# SparkFun_FT245-Breakout.net
KiCad netlist of a schematic drawn in EAGLE
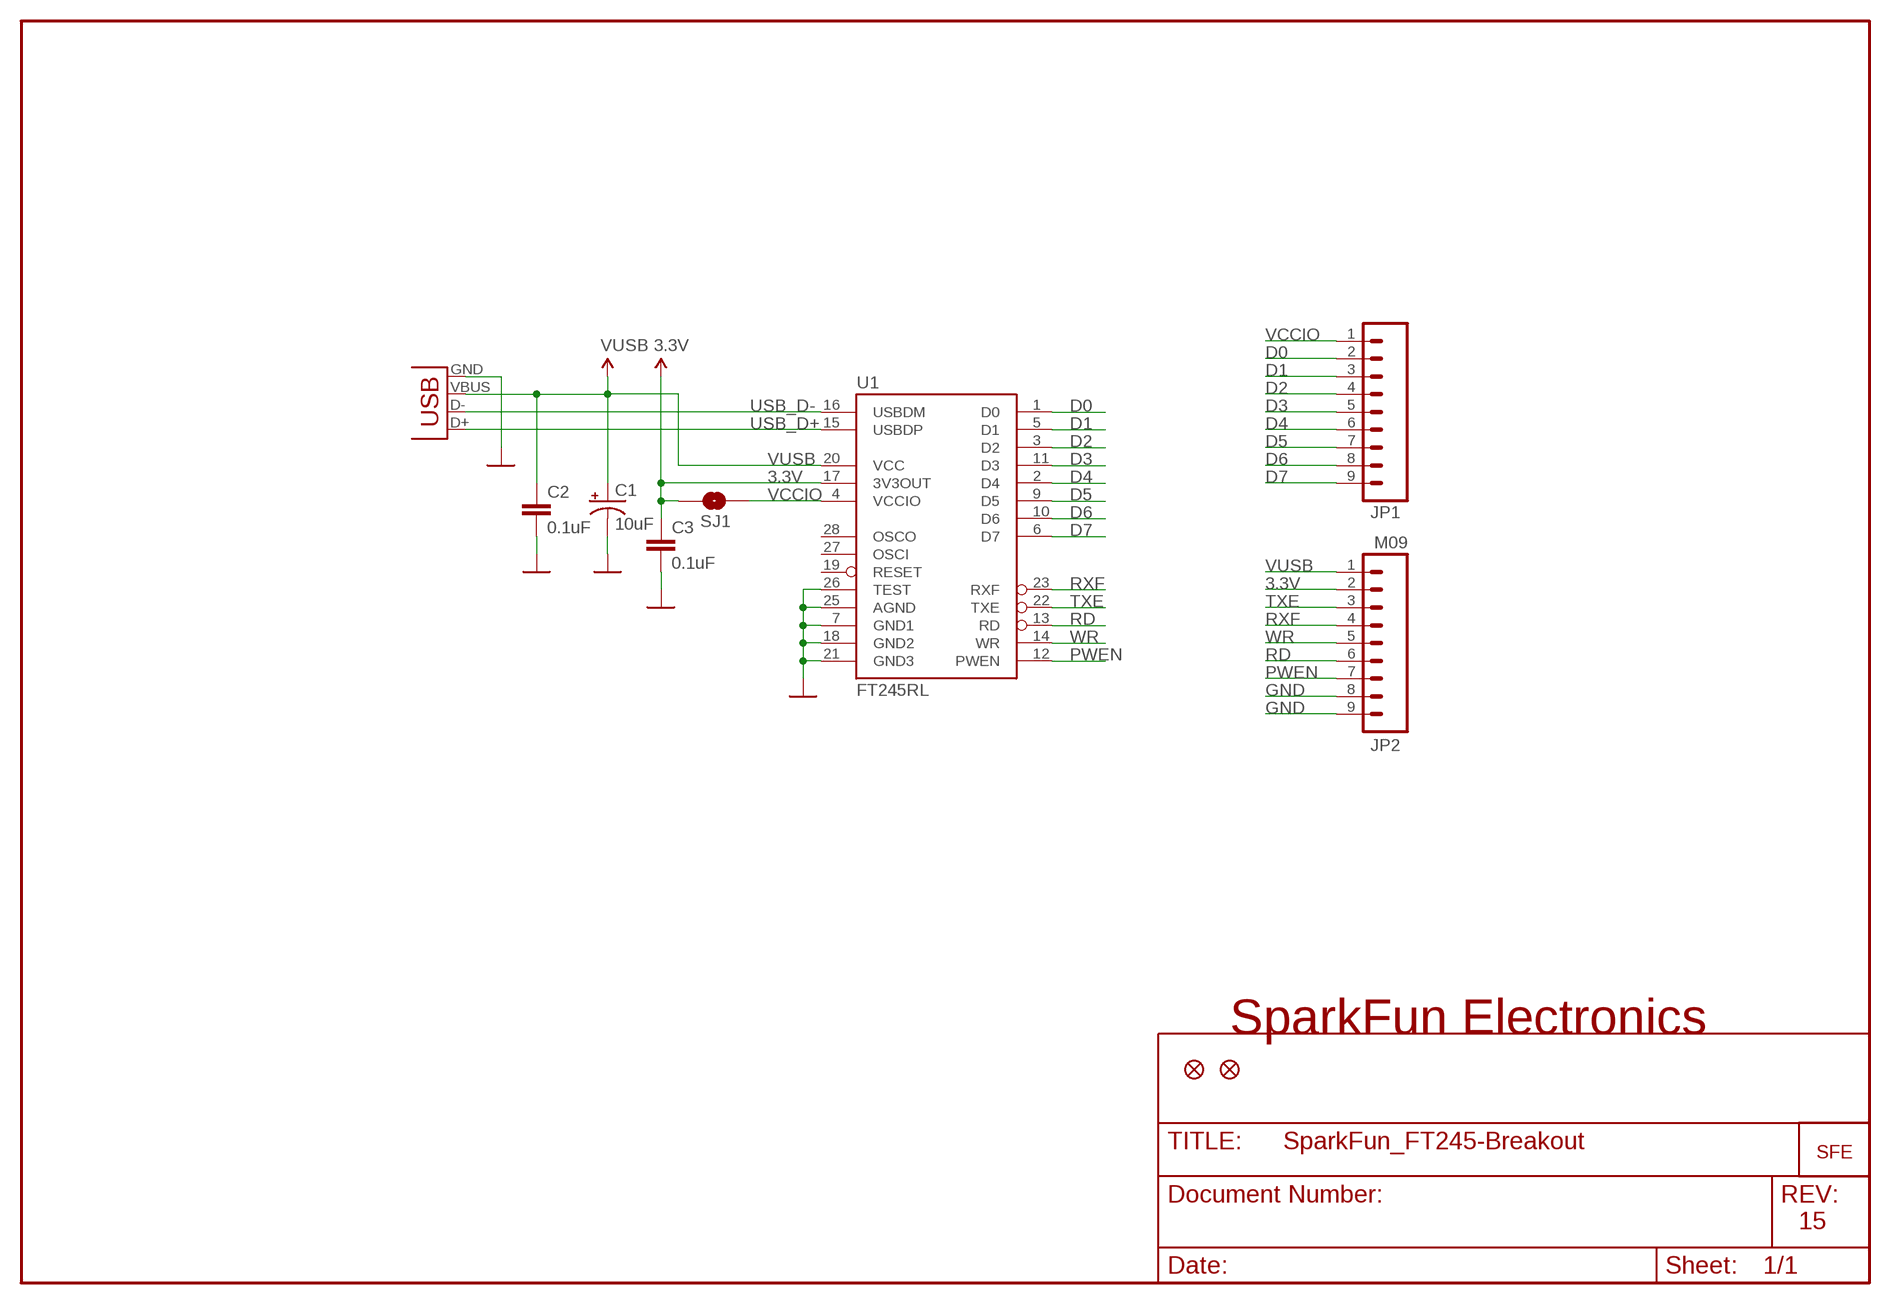
[diagram p0: schematic, sheet 1]

(export (version "E")
  (design (tool "Eeschema 10.0.6"))
  (components
    (comp (ref "C1")
      (value "10uF")
      (footprint "eagle-import:CPOL_1206")
      (libsource (lib "eagle-import") (part "CAP_POL1206"))
    )
    (comp (ref "C2")
      (value "0.1uF")
      (footprint "eagle-import:0402-CAP")
      (libsource (lib "eagle-import") (part "CAP0402-CAP"))
    )
    (comp (ref "C3")
      (value "0.1uF")
      (footprint "eagle-import:0402-CAP")
      (libsource (lib "eagle-import") (part "CAP0402-CAP"))
    )
    (comp (ref "JP1")
      (value "M09")
      (footprint "eagle-import:1X09")
      (libsource (lib "eagle-import") (part "M09"))
    )
    (comp (ref "JP2")
      (value "M09")
      (footprint "eagle-import:1X09")
      (libsource (lib "eagle-import") (part "M09"))
    )
    (comp (ref "JP3")
      (value "FIDUCIAL1X2")
      (footprint "eagle-import:FIDUCIAL-1X2")
      (libsource (lib "eagle-import") (part "FIDUCIAL1X2"))
    )
    (comp (ref "JP4")
      (value "FIDUCIAL1X2")
      (footprint "eagle-import:FIDUCIAL-1X2")
      (libsource (lib "eagle-import") (part "FIDUCIAL1X2"))
    )
    (comp (ref "SJ1")
      (value "SOLDERJUMPERNC2")
      (footprint "eagle-import:SJ_2S-NOTRACE")
      (libsource (lib "eagle-import") (part "SOLDERJUMPERNC2"))
    )
    (comp (ref "U$1")
      (value "LOGO-SFENEW")
      (footprint "eagle-import:SFE-NEW-WEBLOGO")
      (libsource (lib "eagle-import") (part "LOGO-SFENEW"))
    )
    (comp (ref "U1")
      (value "FT245RL")
      (footprint "eagle-import:SSOP28DB")
      (libsource (lib "eagle-import") (part "FT245RL"))
    )
    (comp (ref "X2")
      (value "USBSMD")
      (footprint "eagle-import:USB-MINIB")
      (libsource (lib "eagle-import") (part "USBSMD"))
    )
  )
  (nets
    (net (code "1") (name "/D0") (class "Default")
      (node (ref "JP1") (pin "2") (pinfunction "2_2") (pintype "passive"))
      (node (ref "U1") (pin "1") (pinfunction "D0_1") (pintype "output"))
    )
    (net (code "2") (name "/D1") (class "Default")
      (node (ref "JP1") (pin "3") (pinfunction "3_3") (pintype "passive"))
      (node (ref "U1") (pin "5") (pinfunction "D1_5") (pintype "input"))
    )
    (net (code "3") (name "/D2") (class "Default")
      (node (ref "JP1") (pin "4") (pinfunction "4_4") (pintype "passive"))
      (node (ref "U1") (pin "3") (pinfunction "D2_3") (pintype "output"))
    )
    (net (code "4") (name "/D3") (class "Default")
      (node (ref "JP1") (pin "5") (pinfunction "5_5") (pintype "passive"))
      (node (ref "U1") (pin "11") (pinfunction "D3_11") (pintype "input"))
    )
    (net (code "5") (name "/D4") (class "Default")
      (node (ref "JP1") (pin "6") (pinfunction "6_6") (pintype "passive"))
      (node (ref "U1") (pin "2") (pinfunction "D4_2") (pintype "output"))
    )
    (net (code "6") (name "/D5") (class "Default")
      (node (ref "JP1") (pin "7") (pinfunction "7_7") (pintype "passive"))
      (node (ref "U1") (pin "9") (pinfunction "D5_9") (pintype "input"))
    )
    (net (code "7") (name "/D6") (class "Default")
      (node (ref "JP1") (pin "8") (pinfunction "8_8") (pintype "passive"))
      (node (ref "U1") (pin "10") (pinfunction "D6_10") (pintype "input"))
    )
    (net (code "8") (name "/D7") (class "Default")
      (node (ref "JP1") (pin "9") (pinfunction "9_9") (pintype "passive"))
      (node (ref "U1") (pin "6") (pinfunction "D7_6") (pintype "input"))
    )
    (net (code "9") (name "/PWEN") (class "Default")
      (node (ref "JP2") (pin "7") (pinfunction "7_7") (pintype "passive"))
      (node (ref "U1") (pin "12") (pinfunction "PWEN_12") (pintype "bidirectional"))
    )
    (net (code "10") (name "/RD") (class "Default")
      (node (ref "JP2") (pin "6") (pinfunction "6_6") (pintype "passive"))
      (node (ref "U1") (pin "13") (pinfunction "RD_13") (pintype "bidirectional"))
    )
    (net (code "11") (name "/RXF") (class "Default")
      (node (ref "JP2") (pin "4") (pinfunction "4_4") (pintype "passive"))
      (node (ref "U1") (pin "23") (pinfunction "RXF_23") (pintype "bidirectional"))
    )
    (net (code "12") (name "/TXE") (class "Default")
      (node (ref "JP2") (pin "3") (pinfunction "3_3") (pintype "passive"))
      (node (ref "U1") (pin "22") (pinfunction "TXE_22") (pintype "bidirectional"))
    )
    (net (code "13") (name "/USB_D+") (class "Default")
      (node (ref "U1") (pin "15") (pinfunction "USBDP_15") (pintype "bidirectional"))
      (node (ref "X2") (pin "D+") (pinfunction "D+_D+") (pintype "bidirectional"))
    )
    (net (code "14") (name "/USB_D-") (class "Default")
      (node (ref "U1") (pin "16") (pinfunction "USBDM_16") (pintype "bidirectional"))
      (node (ref "X2") (pin "D-") (pinfunction "D-_D-") (pintype "bidirectional"))
    )
    (net (code "15") (name "/VCCIO") (class "Default")
      (node (ref "JP1") (pin "1") (pinfunction "1_1") (pintype "passive"))
      (node (ref "SJ1") (pin "2") (pinfunction "2_2") (pintype "passive"))
      (node (ref "U1") (pin "4") (pinfunction "VCCIO_4") (pintype "power_in"))
    )
    (net (code "16") (name "/WR") (class "Default")
      (node (ref "JP2") (pin "5") (pinfunction "5_5") (pintype "passive"))
      (node (ref "U1") (pin "14") (pinfunction "WR_14") (pintype "bidirectional"))
    )
    (net (code "17") (name "3.3V") (class "Default")
      (node (ref "C3") (pin "1") (pinfunction "1_1") (pintype "passive"))
      (node (ref "JP2") (pin "2") (pinfunction "2_2") (pintype "passive"))
      (node (ref "SJ1") (pin "1") (pinfunction "1_1") (pintype "passive"))
      (node (ref "U1") (pin "17") (pinfunction "3V3OUT_17") (pintype "output"))
    )
    (net (code "18") (name "GND") (class "Default")
      (node (ref "C1") (pin "C") (pinfunction "-_C") (pintype "passive"))
      (node (ref "C2") (pin "2") (pinfunction "2_2") (pintype "passive"))
      (node (ref "C3") (pin "2") (pinfunction "2_2") (pintype "passive"))
      (node (ref "JP2") (pin "8") (pinfunction "8_8") (pintype "passive"))
      (node (ref "JP2") (pin "9") (pinfunction "9_9") (pintype "passive"))
      (node (ref "U1") (pin "18") (pinfunction "GND2_18") (pintype "power_in"))
      (node (ref "U1") (pin "21") (pinfunction "GND3_21") (pintype "power_in"))
      (node (ref "U1") (pin "25") (pinfunction "AGND_25") (pintype "power_in"))
      (node (ref "U1") (pin "26") (pinfunction "TEST_26") (pintype "input"))
      (node (ref "U1") (pin "7") (pinfunction "GND1_7") (pintype "power_in"))
      (node (ref "X2") (pin "GND") (pinfunction "GND_GND") (pintype "bidirectional"))
    )
    (net (code "19") (name "VUSB") (class "Default")
      (node (ref "C1") (pin "A") (pinfunction "+_A") (pintype "passive"))
      (node (ref "C2") (pin "1") (pinfunction "1_1") (pintype "passive"))
      (node (ref "JP2") (pin "1") (pinfunction "1_1") (pintype "passive"))
      (node (ref "U1") (pin "20") (pinfunction "VCC_20") (pintype "power_in"))
      (node (ref "X2") (pin "VBUS") (pinfunction "VBUS_VBUS") (pintype "bidirectional"))
    )
    (net (code "20") (name "unconnected-(U1-OSCI-Pad27)") (class "Default")
      (node (ref "U1") (pin "27") (pinfunction "OSCI_27") (pintype "input"))
    )
    (net (code "21") (name "unconnected-(U1-OSCO-Pad28)") (class "Default")
      (node (ref "U1") (pin "28") (pinfunction "OSCO_28") (pintype "output"))
    )
    (net (code "22") (name "unconnected-(U1-RESET-Pad19)") (class "Default")
      (node (ref "U1") (pin "19") (pinfunction "RESET_19") (pintype "input"))
    )
  )
)
